# AOA-control-revD-sink.net
KiCad netlist of a schematic drawn in EAGLE
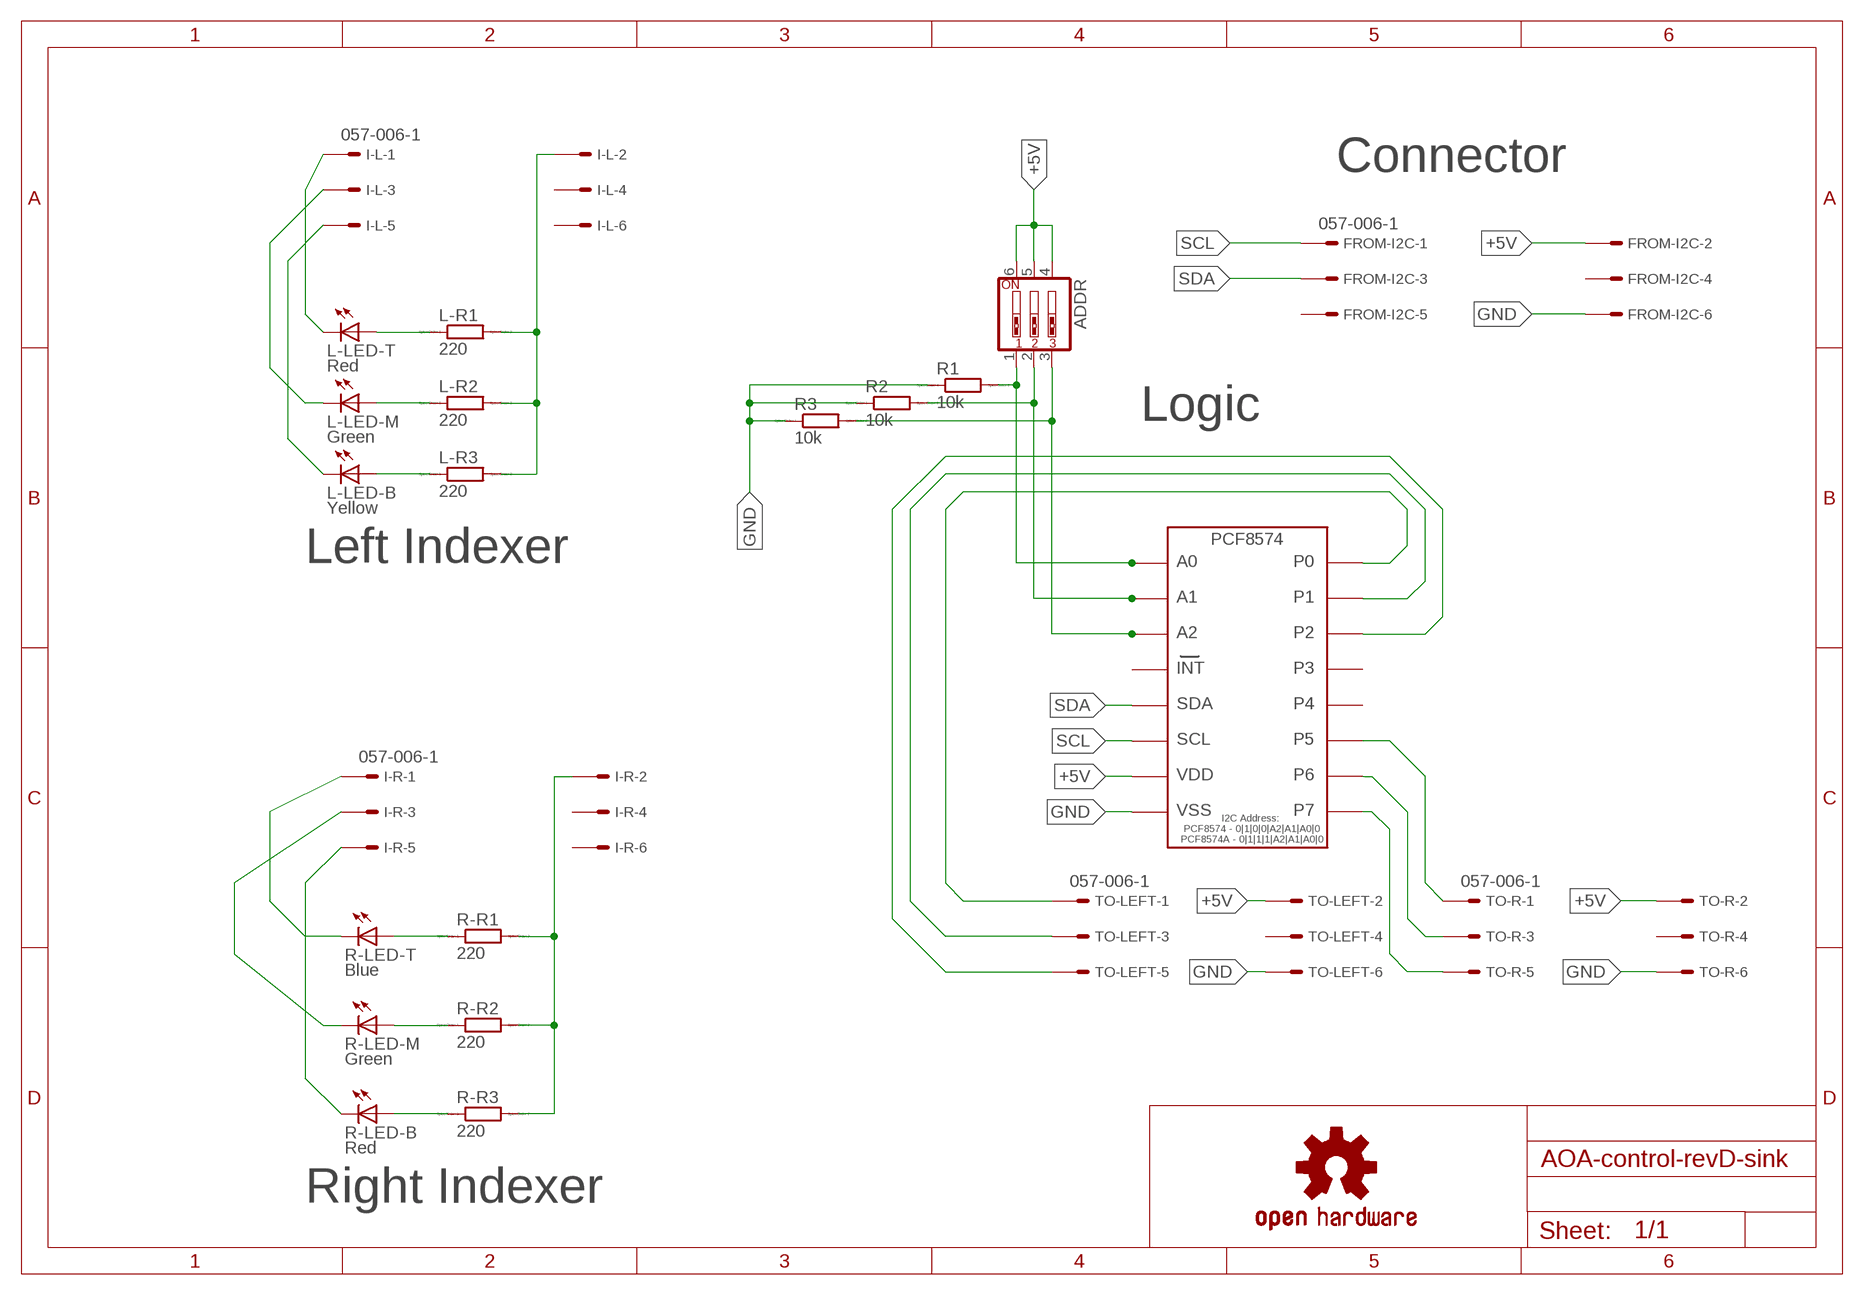
[diagram p0: schematic, sheet 1]

(export (version "E")
  (design (tool "Eeschema 10.0.6"))
  (components
    (comp (ref "ADDR")
      (value "SW_DIP-3")
      (footprint "eagle-import:EDG-03")
      (libsource (lib "eagle-import") (part "SW_DIP-3"))
    )
    (comp (ref "FROM-I2C")
      (value "057-006-1")
      (footprint "eagle-import:057-006-1")
      (libsource (lib "eagle-import") (part "057-006-1"))
    )
    (comp (ref "I-L")
      (value "057-006-1")
      (footprint "eagle-import:057-006-1")
      (libsource (lib "eagle-import") (part "057-006-1"))
    )
    (comp (ref "I-R")
      (value "057-006-1")
      (footprint "eagle-import:057-006-1")
      (libsource (lib "eagle-import") (part "057-006-1"))
    )
    (comp (ref "L-LED-B")
      (value "Yellow")
      (footprint "eagle-import:CP41B")
      (libsource (lib "eagle-import") (part "LED-2AC-CP41B-WGS"))
    )
    (comp (ref "L-LED-M")
      (value "Green")
      (footprint "eagle-import:CP41B")
      (libsource (lib "eagle-import") (part "LED-2AC-CP41B-WGS"))
    )
    (comp (ref "L-LED-T")
      (value "Red")
      (footprint "eagle-import:CP41B")
      (libsource (lib "eagle-import") (part "LED-2AC-CP41B-WGS"))
    )
    (comp (ref "L-R1")
      (value "220")
      (footprint "eagle-import:0204_7")
      (libsource (lib "eagle-import") (part "R0204/7"))
    )
    (comp (ref "L-R2")
      (value "220")
      (footprint "eagle-import:0204_7")
      (libsource (lib "eagle-import") (part "R0204/7"))
    )
    (comp (ref "L-R3")
      (value "220")
      (footprint "eagle-import:0204_7")
      (libsource (lib "eagle-import") (part "R0204/7"))
    )
    (comp (ref "LOGO1")
      (value "OSHW-LOGOS")
      (footprint "eagle-import:OSHW-LOGO-S")
      (libsource (lib "eagle-import") (part "OSHW-LOGOS"))
    )
    (comp (ref "R-LED-B")
      (value "Red")
      (footprint "eagle-import:CP41B")
      (libsource (lib "eagle-import") (part "LED-2AC-CP41B-WGS"))
    )
    (comp (ref "R-LED-M")
      (value "Green")
      (footprint "eagle-import:CP41B")
      (libsource (lib "eagle-import") (part "LED-2AC-CP41B-WGS"))
    )
    (comp (ref "R-LED-T")
      (value "Blue")
      (footprint "eagle-import:CP41B")
      (libsource (lib "eagle-import") (part "LED-2AC-CP41B-WGS"))
    )
    (comp (ref "R-R1")
      (value "220")
      (footprint "eagle-import:0204_7")
      (libsource (lib "eagle-import") (part "R0204/7"))
    )
    (comp (ref "R-R2")
      (value "220")
      (footprint "eagle-import:0204_7")
      (libsource (lib "eagle-import") (part "R0204/7"))
    )
    (comp (ref "R-R3")
      (value "220")
      (footprint "eagle-import:0204_7")
      (libsource (lib "eagle-import") (part "R0204/7"))
    )
    (comp (ref "R1")
      (value "10k")
      (footprint "eagle-import:0204_7")
      (libsource (lib "eagle-import") (part "R0204/7"))
    )
    (comp (ref "R2")
      (value "10k")
      (footprint "eagle-import:0204_7")
      (libsource (lib "eagle-import") (part "R0204/7"))
    )
    (comp (ref "R3")
      (value "10k")
      (footprint "eagle-import:0204_7")
      (libsource (lib "eagle-import") (part "R0204/7"))
    )
    (comp (ref "TO-LEFT")
      (value "057-006-1")
      (footprint "eagle-import:057-006-1")
      (libsource (lib "eagle-import") (part "057-006-1"))
    )
    (comp (ref "TO-R")
      (value "057-006-1")
      (footprint "eagle-import:057-006-1")
      (libsource (lib "eagle-import") (part "057-006-1"))
    )
    (comp (ref "U$1")
      (value "PCF8574P/AP")
      (footprint "eagle-import:DIP16")
      (libsource (lib "eagle-import") (part "PCF8574P/AP"))
    )
  )
  (nets
    (net (code "1") (name "+5V") (class "Default")
      (node (ref "ADDR") (pin "4") (pinfunction "4_4") (pintype "passive"))
      (node (ref "ADDR") (pin "5") (pinfunction "5_5") (pintype "passive"))
      (node (ref "ADDR") (pin "6") (pinfunction "6_6") (pintype "passive"))
      (node (ref "FROM-I2C") (pin "2") (pinfunction "S_2") (pintype "passive"))
      (node (ref "TO-LEFT") (pin "2") (pinfunction "S_2") (pintype "passive"))
      (node (ref "TO-R") (pin "2") (pinfunction "S_2") (pintype "passive"))
      (node (ref "U$1") (pin "VDD") (pinfunction "VDD_VDD") (pintype "bidirectional"))
    )
    (net (code "2") (name "GND") (class "Default")
      (node (ref "FROM-I2C") (pin "6") (pinfunction "S_6") (pintype "passive"))
      (node (ref "R1") (pin "1") (pinfunction "1_1") (pintype "passive"))
      (node (ref "R2") (pin "1") (pinfunction "1_1") (pintype "passive"))
      (node (ref "R3") (pin "1") (pinfunction "1_1") (pintype "passive"))
      (node (ref "TO-LEFT") (pin "6") (pinfunction "S_6") (pintype "passive"))
      (node (ref "TO-R") (pin "6") (pinfunction "S_6") (pintype "passive"))
      (node (ref "U$1") (pin "VSS") (pinfunction "VSS_VSS") (pintype "bidirectional"))
    )
    (net (code "3") (name "Net-(ADDR-Pad1)") (class "Default")
      (node (ref "ADDR") (pin "1") (pinfunction "1_1") (pintype "passive"))
      (node (ref "R1") (pin "2") (pinfunction "2_2") (pintype "passive"))
      (node (ref "U$1") (pin "A0") (pinfunction "A0_A0") (pintype "bidirectional"))
    )
    (net (code "4") (name "Net-(ADDR-Pad2)") (class "Default")
      (node (ref "ADDR") (pin "2") (pinfunction "2_2") (pintype "passive"))
      (node (ref "R2") (pin "2") (pinfunction "2_2") (pintype "passive"))
      (node (ref "U$1") (pin "A1") (pinfunction "A1_A1") (pintype "bidirectional"))
    )
    (net (code "5") (name "Net-(ADDR-Pad3)") (class "Default")
      (node (ref "ADDR") (pin "3") (pinfunction "3_3") (pintype "passive"))
      (node (ref "R3") (pin "2") (pinfunction "2_2") (pintype "passive"))
      (node (ref "U$1") (pin "A2") (pinfunction "A2_A2") (pintype "bidirectional"))
    )
    (net (code "6") (name "Net-(I-LA-S)") (class "Default")
      (node (ref "I-L") (pin "1") (pinfunction "S_1") (pintype "passive"))
      (node (ref "L-LED-T") (pin "1") (pinfunction "C_1") (pintype "passive"))
      (node (ref "L-LED-T") (pin "4") (pinfunction "C_4") (pintype "passive"))
    )
    (net (code "7") (name "Net-(I-LB-S)") (class "Default")
      (node (ref "I-L") (pin "2") (pinfunction "S_2") (pintype "passive"))
      (node (ref "L-R1") (pin "2") (pinfunction "2_2") (pintype "passive"))
      (node (ref "L-R2") (pin "2") (pinfunction "2_2") (pintype "passive"))
      (node (ref "L-R3") (pin "2") (pinfunction "2_2") (pintype "passive"))
    )
    (net (code "8") (name "Net-(I-LC-S)") (class "Default")
      (node (ref "I-L") (pin "3") (pinfunction "S_3") (pintype "passive"))
      (node (ref "L-LED-M") (pin "1") (pinfunction "C_1") (pintype "passive"))
      (node (ref "L-LED-M") (pin "4") (pinfunction "C_4") (pintype "passive"))
    )
    (net (code "9") (name "Net-(I-LE-S)") (class "Default")
      (node (ref "I-L") (pin "5") (pinfunction "S_5") (pintype "passive"))
      (node (ref "L-LED-B") (pin "1") (pinfunction "C_1") (pintype "passive"))
      (node (ref "L-LED-B") (pin "4") (pinfunction "C_4") (pintype "passive"))
    )
    (net (code "10") (name "Net-(I-RA-S)") (class "Default")
      (node (ref "I-R") (pin "1") (pinfunction "S_1") (pintype "passive"))
      (node (ref "R-LED-T") (pin "1") (pinfunction "C_1") (pintype "passive"))
      (node (ref "R-LED-T") (pin "4") (pinfunction "C_4") (pintype "passive"))
    )
    (net (code "11") (name "Net-(I-RB-S)") (class "Default")
      (node (ref "I-R") (pin "2") (pinfunction "S_2") (pintype "passive"))
      (node (ref "R-R1") (pin "2") (pinfunction "2_2") (pintype "passive"))
      (node (ref "R-R2") (pin "2") (pinfunction "2_2") (pintype "passive"))
      (node (ref "R-R3") (pin "2") (pinfunction "2_2") (pintype "passive"))
    )
    (net (code "12") (name "Net-(I-RC-S)") (class "Default")
      (node (ref "I-R") (pin "3") (pinfunction "S_3") (pintype "passive"))
      (node (ref "R-LED-M") (pin "1") (pinfunction "C_1") (pintype "passive"))
      (node (ref "R-LED-M") (pin "4") (pinfunction "C_4") (pintype "passive"))
    )
    (net (code "13") (name "Net-(I-RE-S)") (class "Default")
      (node (ref "I-R") (pin "5") (pinfunction "S_5") (pintype "passive"))
      (node (ref "R-LED-B") (pin "1") (pinfunction "C_1") (pintype "passive"))
      (node (ref "R-LED-B") (pin "4") (pinfunction "C_4") (pintype "passive"))
    )
    (net (code "14") (name "Net-(L-LED-B-A-Pad2)") (class "Default")
      (node (ref "L-LED-B") (pin "2") (pinfunction "A_2") (pintype "passive"))
      (node (ref "L-LED-B") (pin "3") (pinfunction "A_3") (pintype "passive"))
      (node (ref "L-R3") (pin "1") (pinfunction "1_1") (pintype "passive"))
    )
    (net (code "15") (name "Net-(L-LED-M-A-Pad2)") (class "Default")
      (node (ref "L-LED-M") (pin "2") (pinfunction "A_2") (pintype "passive"))
      (node (ref "L-LED-M") (pin "3") (pinfunction "A_3") (pintype "passive"))
      (node (ref "L-R2") (pin "1") (pinfunction "1_1") (pintype "passive"))
    )
    (net (code "16") (name "Net-(L-LED-T-A-Pad2)") (class "Default")
      (node (ref "L-LED-T") (pin "2") (pinfunction "A_2") (pintype "passive"))
      (node (ref "L-LED-T") (pin "3") (pinfunction "A_3") (pintype "passive"))
      (node (ref "L-R1") (pin "1") (pinfunction "1_1") (pintype "passive"))
    )
    (net (code "17") (name "Net-(R-LED-B-A-Pad2)") (class "Default")
      (node (ref "R-LED-B") (pin "2") (pinfunction "A_2") (pintype "passive"))
      (node (ref "R-LED-B") (pin "3") (pinfunction "A_3") (pintype "passive"))
      (node (ref "R-R3") (pin "1") (pinfunction "1_1") (pintype "passive"))
    )
    (net (code "18") (name "Net-(R-LED-M-A-Pad2)") (class "Default")
      (node (ref "R-LED-M") (pin "2") (pinfunction "A_2") (pintype "passive"))
      (node (ref "R-LED-M") (pin "3") (pinfunction "A_3") (pintype "passive"))
      (node (ref "R-R2") (pin "1") (pinfunction "1_1") (pintype "passive"))
    )
    (net (code "19") (name "Net-(R-LED-T-A-Pad2)") (class "Default")
      (node (ref "R-LED-T") (pin "2") (pinfunction "A_2") (pintype "passive"))
      (node (ref "R-LED-T") (pin "3") (pinfunction "A_3") (pintype "passive"))
      (node (ref "R-R1") (pin "1") (pinfunction "1_1") (pintype "passive"))
    )
    (net (code "20") (name "Net-(TO-LEFTA-S)") (class "Default")
      (node (ref "TO-LEFT") (pin "1") (pinfunction "S_1") (pintype "passive"))
      (node (ref "U$1") (pin "P0") (pinfunction "P0_P0") (pintype "bidirectional"))
    )
    (net (code "21") (name "Net-(TO-LEFTC-S)") (class "Default")
      (node (ref "TO-LEFT") (pin "3") (pinfunction "S_3") (pintype "passive"))
      (node (ref "U$1") (pin "P1") (pinfunction "P1_P1") (pintype "bidirectional"))
    )
    (net (code "22") (name "Net-(TO-LEFTE-S)") (class "Default")
      (node (ref "TO-LEFT") (pin "5") (pinfunction "S_5") (pintype "passive"))
      (node (ref "U$1") (pin "P2") (pinfunction "P2_P2") (pintype "bidirectional"))
    )
    (net (code "23") (name "Net-(TO-RA-S)") (class "Default")
      (node (ref "TO-R") (pin "1") (pinfunction "S_1") (pintype "passive"))
      (node (ref "U$1") (pin "P5") (pinfunction "P5_P5") (pintype "bidirectional"))
    )
    (net (code "24") (name "Net-(TO-RC-S)") (class "Default")
      (node (ref "TO-R") (pin "3") (pinfunction "S_3") (pintype "passive"))
      (node (ref "U$1") (pin "P6") (pinfunction "P6_P6") (pintype "bidirectional"))
    )
    (net (code "25") (name "Net-(TO-RE-S)") (class "Default")
      (node (ref "TO-R") (pin "5") (pinfunction "S_5") (pintype "passive"))
      (node (ref "U$1") (pin "P7") (pinfunction "P7_P7") (pintype "bidirectional"))
    )
    (net (code "26") (name "SCL") (class "Default")
      (node (ref "FROM-I2C") (pin "1") (pinfunction "S_1") (pintype "passive"))
      (node (ref "U$1") (pin "SCL") (pinfunction "SCL_SCL") (pintype "bidirectional"))
    )
    (net (code "27") (name "SDA") (class "Default")
      (node (ref "FROM-I2C") (pin "3") (pinfunction "S_3") (pintype "passive"))
      (node (ref "U$1") (pin "SDA") (pinfunction "SDA_SDA") (pintype "bidirectional"))
    )
    (net (code "28") (name "unconnected-(FROM-I2CD-S-Pad4)") (class "Default")
      (node (ref "FROM-I2C") (pin "4") (pinfunction "S_4") (pintype "passive"))
    )
    (net (code "29") (name "unconnected-(FROM-I2CE-S-Pad5)") (class "Default")
      (node (ref "FROM-I2C") (pin "5") (pinfunction "S_5") (pintype "passive"))
    )
    (net (code "30") (name "unconnected-(I-LD-S-Pad4)") (class "Default")
      (node (ref "I-L") (pin "4") (pinfunction "S_4") (pintype "passive"))
    )
    (net (code "31") (name "unconnected-(I-LF-S-Pad6)") (class "Default")
      (node (ref "I-L") (pin "6") (pinfunction "S_6") (pintype "passive"))
    )
    (net (code "32") (name "unconnected-(I-RD-S-Pad4)") (class "Default")
      (node (ref "I-R") (pin "4") (pinfunction "S_4") (pintype "passive"))
    )
    (net (code "33") (name "unconnected-(I-RF-S-Pad6)") (class "Default")
      (node (ref "I-R") (pin "6") (pinfunction "S_6") (pintype "passive"))
    )
    (net (code "34") (name "unconnected-(TO-LEFTD-S-Pad4)") (class "Default")
      (node (ref "TO-LEFT") (pin "4") (pinfunction "S_4") (pintype "passive"))
    )
    (net (code "35") (name "unconnected-(TO-RD-S-Pad4)") (class "Default")
      (node (ref "TO-R") (pin "4") (pinfunction "S_4") (pintype "passive"))
    )
    (net (code "36") (name "unconnected-(U$1-PadINT)") (class "Default")
      (node (ref "U$1") (pin "INT") (pinfunction "INT_INT") (pintype "bidirectional"))
    )
    (net (code "37") (name "unconnected-(U$1-PadP3)") (class "Default")
      (node (ref "U$1") (pin "P3") (pinfunction "P3_P3") (pintype "bidirectional"))
    )
    (net (code "38") (name "unconnected-(U$1-PadP4)") (class "Default")
      (node (ref "U$1") (pin "P4") (pinfunction "P4_P4") (pintype "bidirectional"))
    )
  )
)
